# Badge_Motor-ExhibitionLarge.net
KiCad netlist of a schematic drawn in EAGLE
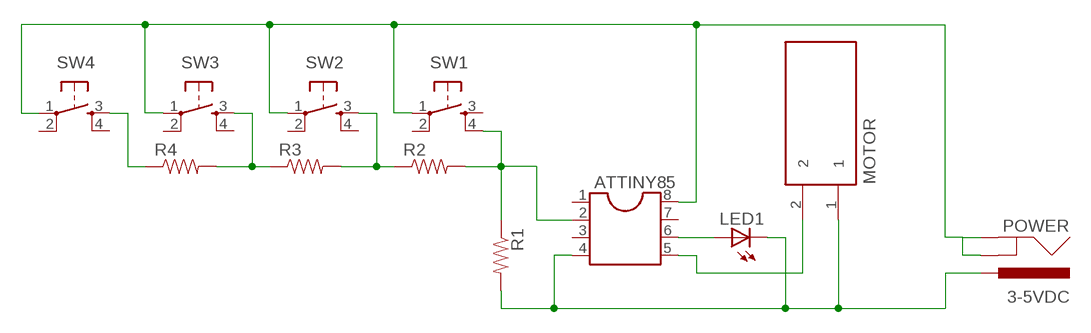
[diagram p0: schematic, sheet 1]

(export (version "E")
  (design (tool "Eeschema 10.0.6"))
  (components
    (comp (ref "ATTINY85")
      (value "DIL8S")
      (footprint "eagle-import:SOCKET-08")
      (libsource (lib "eagle-import") (part "DIL8S"))
    )
    (comp (ref "LED1")
      (value "LEDCHIPLED_0805")
      (footprint "eagle-import:CHIPLED_0805")
      (libsource (lib "eagle-import") (part "LEDCHIPLED_0805"))
    )
    (comp (ref "MOTOR")
      (value "VIB-MOTOR")
      (footprint "eagle-import:VIB-MOTOR")
      (libsource (lib "eagle-import") (part "VIB-MOTOR"))
    )
    (comp (ref "POWER")
      (value "3-5VDC")
      (footprint "eagle-import:POWER_JACK_SMD")
      (libsource (lib "eagle-import") (part "POWER_JACKSMD"))
    )
    (comp (ref "R1")
      (value "RESISTOR2010")
      (footprint "eagle-import:R2010")
      (libsource (lib "eagle-import") (part "RESISTOR2010"))
    )
    (comp (ref "R2")
      (value "RESISTOR2010")
      (footprint "eagle-import:R2010")
      (libsource (lib "eagle-import") (part "RESISTOR2010"))
    )
    (comp (ref "R3")
      (value "RESISTOR2010")
      (footprint "eagle-import:R2010")
      (libsource (lib "eagle-import") (part "RESISTOR2010"))
    )
    (comp (ref "R4")
      (value "RESISTOR2010")
      (footprint "eagle-import:R2010")
      (libsource (lib "eagle-import") (part "RESISTOR2010"))
    )
    (comp (ref "SW1")
      (value "TAC_SWITCHPTH")
      (footprint "eagle-import:TACTILE-PTH")
      (libsource (lib "eagle-import") (part "TAC_SWITCHPTH"))
    )
    (comp (ref "SW2")
      (value "TAC_SWITCHPTH")
      (footprint "eagle-import:TACTILE-PTH")
      (libsource (lib "eagle-import") (part "TAC_SWITCHPTH"))
    )
    (comp (ref "SW3")
      (value "TAC_SWITCHPTH")
      (footprint "eagle-import:TACTILE-PTH")
      (libsource (lib "eagle-import") (part "TAC_SWITCHPTH"))
    )
    (comp (ref "SW4")
      (value "TAC_SWITCHPTH")
      (footprint "eagle-import:TACTILE-PTH")
      (libsource (lib "eagle-import") (part "TAC_SWITCHPTH"))
    )
  )
  (nets
    (net (code "1") (name "Net-(ATTINY85-Pad2)") (class "Default")
      (node (ref "ATTINY85") (pin "2") (pinfunction "2_2") (pintype "passive"))
      (node (ref "R1") (pin "1") (pinfunction "1_1") (pintype "passive"))
      (node (ref "R2") (pin "2") (pinfunction "2_2") (pintype "passive"))
      (node (ref "SW1") (pin "4") (pinfunction "4_4") (pintype "passive"))
    )
    (net (code "2") (name "Net-(ATTINY85-Pad5)") (class "Default")
      (node (ref "ATTINY85") (pin "5") (pinfunction "5_5") (pintype "passive"))
      (node (ref "MOTOR") (pin "2") (pinfunction "2_2") (pintype "bidirectional"))
    )
    (net (code "3") (name "Net-(ATTINY85-Pad6)") (class "Default")
      (node (ref "ATTINY85") (pin "6") (pinfunction "6_6") (pintype "passive"))
      (node (ref "LED1") (pin "A") (pinfunction "A_A") (pintype "passive"))
    )
    (net (code "4") (name "Net-(POWER-GND)") (class "Default")
      (node (ref "ATTINY85") (pin "8") (pinfunction "8_8") (pintype "passive"))
      (node (ref "POWER") (pin "GND") (pinfunction "GNDBREAK_GND") (pintype "bidirectional"))
      (node (ref "POWER") (pin "P$4") (pinfunction "GND_P$4") (pintype "bidirectional"))
      (node (ref "SW1") (pin "1") (pinfunction "1_1") (pintype "passive"))
      (node (ref "SW2") (pin "1") (pinfunction "1_1") (pintype "passive"))
      (node (ref "SW3") (pin "1") (pinfunction "1_1") (pintype "passive"))
      (node (ref "SW4") (pin "1") (pinfunction "1_1") (pintype "passive"))
    )
    (net (code "5") (name "Net-(POWER-PWR)") (class "Default")
      (node (ref "ATTINY85") (pin "4") (pinfunction "4_4") (pintype "passive"))
      (node (ref "LED1") (pin "C") (pinfunction "C_C") (pintype "passive"))
      (node (ref "MOTOR") (pin "1") (pinfunction "1_1") (pintype "bidirectional"))
      (node (ref "POWER") (pin "VIN0") (pinfunction "PWR_VIN0") (pintype "bidirectional"))
      (node (ref "R1") (pin "2") (pinfunction "2_2") (pintype "passive"))
    )
    (net (code "6") (name "Net-(R2-Pad1)") (class "Default")
      (node (ref "R2") (pin "1") (pinfunction "1_1") (pintype "passive"))
      (node (ref "R3") (pin "2") (pinfunction "2_2") (pintype "passive"))
      (node (ref "SW2") (pin "3") (pinfunction "3_3") (pintype "passive"))
    )
    (net (code "7") (name "Net-(R3-Pad1)") (class "Default")
      (node (ref "R3") (pin "1") (pinfunction "1_1") (pintype "passive"))
      (node (ref "R4") (pin "2") (pinfunction "2_2") (pintype "passive"))
      (node (ref "SW3") (pin "3") (pinfunction "3_3") (pintype "passive"))
    )
    (net (code "8") (name "Net-(R4-Pad1)") (class "Default")
      (node (ref "R4") (pin "1") (pinfunction "1_1") (pintype "passive"))
      (node (ref "SW4") (pin "3") (pinfunction "3_3") (pintype "passive"))
    )
    (net (code "9") (name "unconnected-(ATTINY85-Pad1)") (class "Default")
      (node (ref "ATTINY85") (pin "1") (pinfunction "1_1") (pintype "passive"))
    )
    (net (code "10") (name "unconnected-(ATTINY85-Pad3)") (class "Default")
      (node (ref "ATTINY85") (pin "3") (pinfunction "3_3") (pintype "passive"))
    )
    (net (code "11") (name "unconnected-(ATTINY85-Pad7)") (class "Default")
      (node (ref "ATTINY85") (pin "7") (pinfunction "7_7") (pintype "passive"))
    )
    (net (code "12") (name "unconnected-(SW1-Pad2)") (class "Default")
      (node (ref "SW1") (pin "2") (pinfunction "2_2") (pintype "passive"))
    )
    (net (code "13") (name "unconnected-(SW1-Pad3)") (class "Default")
      (node (ref "SW1") (pin "3") (pinfunction "3_3") (pintype "passive"))
    )
    (net (code "14") (name "unconnected-(SW2-Pad2)") (class "Default")
      (node (ref "SW2") (pin "2") (pinfunction "2_2") (pintype "passive"))
    )
    (net (code "15") (name "unconnected-(SW2-Pad4)") (class "Default")
      (node (ref "SW2") (pin "4") (pinfunction "4_4") (pintype "passive"))
    )
    (net (code "16") (name "unconnected-(SW3-Pad2)") (class "Default")
      (node (ref "SW3") (pin "2") (pinfunction "2_2") (pintype "passive"))
    )
    (net (code "17") (name "unconnected-(SW3-Pad4)") (class "Default")
      (node (ref "SW3") (pin "4") (pinfunction "4_4") (pintype "passive"))
    )
    (net (code "18") (name "unconnected-(SW4-Pad2)") (class "Default")
      (node (ref "SW4") (pin "2") (pinfunction "2_2") (pintype "passive"))
    )
    (net (code "19") (name "unconnected-(SW4-Pad4)") (class "Default")
      (node (ref "SW4") (pin "4") (pinfunction "4_4") (pintype "passive"))
    )
  )
)
